# ACT_REG.net
KiCad netlist of a schematic drawn in Altium Designer
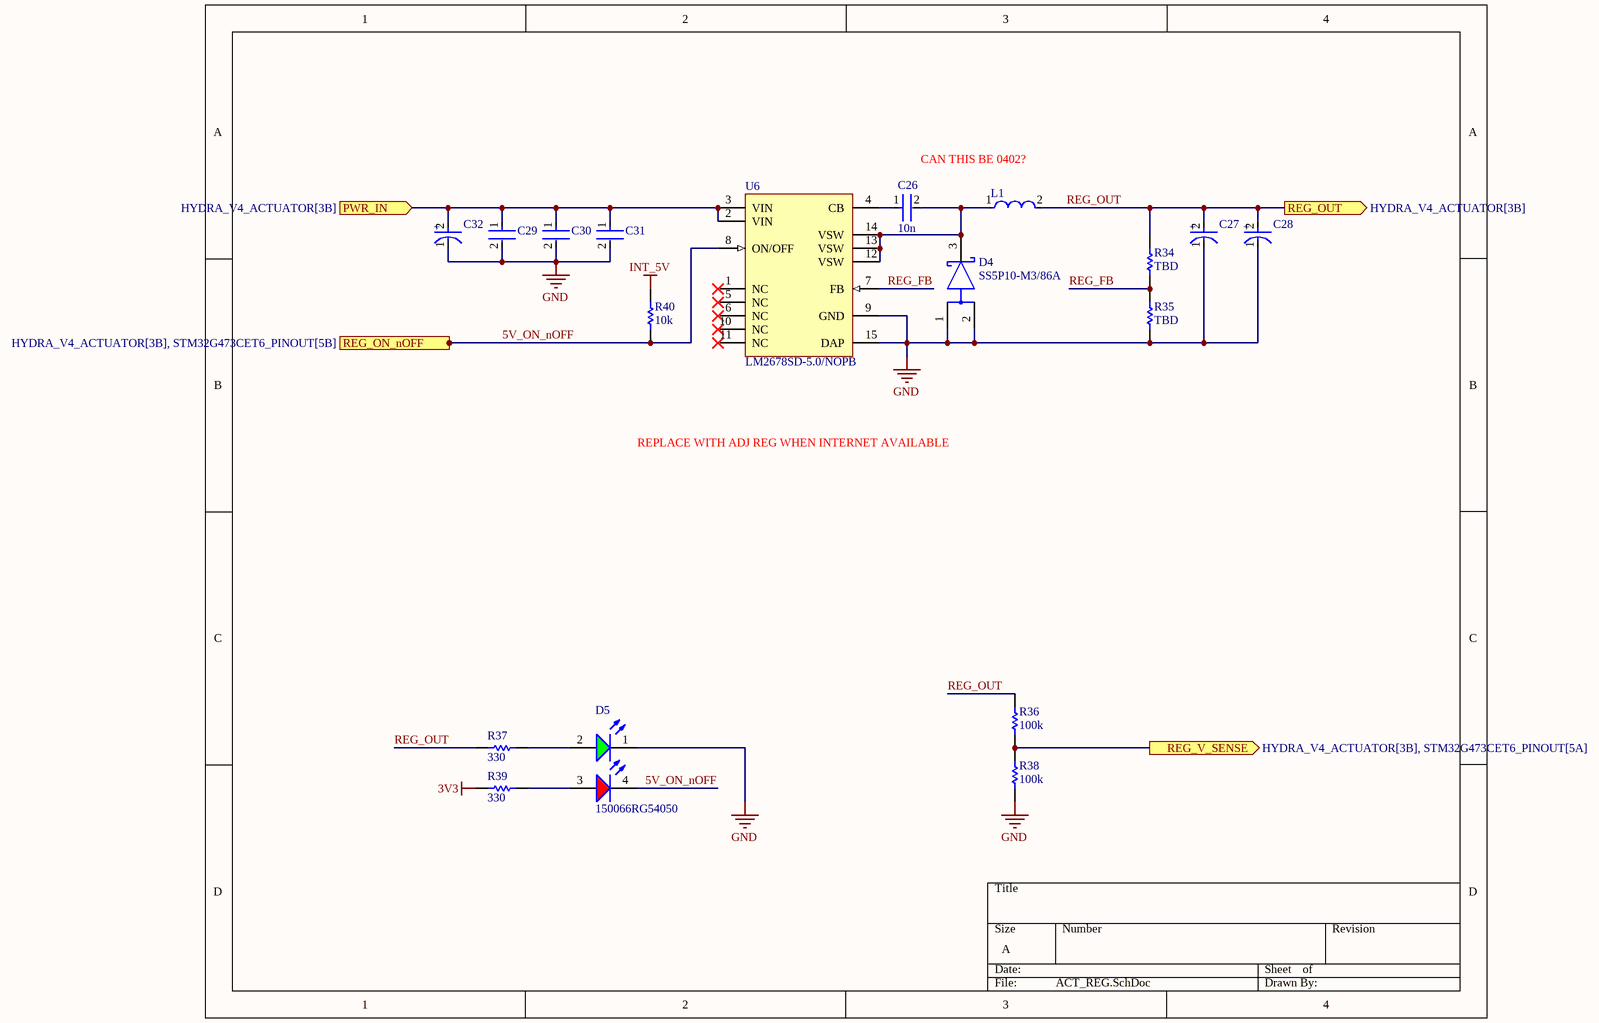
[diagram p0: ACT_REG.SchDoc]

(export (version "E")
  (design (tool "Eeschema 10.0.6"))
  (components
    (comp (ref "C26")
      (value "10n")
      (footprint "FP-0402-L_1_0_0_05-W_0_5-IPC_A")
      (description "LARGE PADS, 0402 CAP, CHANGE COMMENT TO MATCH REAL P/N")
      (libsource (lib "Space Concordia") (part "b4654b650e69147ec39a6b967a45e02"))
    )
    (comp (ref "C27")
      (value "10TPC68M")
      (footprint "FP-POSCAP-D2-MFG")
      (description "Molded Tantalum Polymer Capacitor 68uF 20% 10V life 2000Hours SMD 2917")
      (fields (field (name "VOLTAGE") "10V") (field (name "TOLERANCE") "20%"))
      (libsource (lib "Altium Content Vault") (part "a00bbbee19879c290e62620ae7e47b1"))
    )
    (comp (ref "C28")
      (value "10TPC68M")
      (footprint "FP-POSCAP-D2-MFG")
      (description "Molded Tantalum Polymer Capacitor 68uF 20% 10V life 2000Hours SMD 2917")
      (fields (field (name "VOLTAGE") "10V") (field (name "TOLERANCE") "20%"))
      (libsource (lib "Altium Content Vault") (part "a00bbbee19879c290e62620ae7e47b1"))
    )
    (comp (ref "C29")
      (value "C2012X5R1V156M125AC")
      (footprint "FP-C2012-125-0_2-MFG")
      (description "Multilayer Ceramic Capacitors 15μF ±20% 35V X5R SMD 0805")
      (fields (field (name "TOLERANCE") "20%"))
      (libsource (lib "Altium Content Vault") (part "b4654b650e69147ec39a6b967a45e02"))
    )
    (comp (ref "C30")
      (value "C2012X5R1V156M125AC")
      (footprint "FP-C2012-125-0_2-MFG")
      (description "Multilayer Ceramic Capacitors 15μF ±20% 35V X5R SMD 0805")
      (fields (field (name "TOLERANCE") "20%"))
      (libsource (lib "Altium Content Vault") (part "b4654b650e69147ec39a6b967a45e02"))
    )
    (comp (ref "C31")
      (value "C2012X5R1V156M125AC")
      (footprint "FP-C2012-125-0_2-MFG")
      (description "Multilayer Ceramic Capacitors 15μF ±20% 35V X5R SMD 0805")
      (fields (field (name "TOLERANCE") "20%"))
      (libsource (lib "Altium Content Vault") (part "b4654b650e69147ec39a6b967a45e02"))
    )
    (comp (ref "C32")
      (value "10TPC68M")
      (footprint "FP-POSCAP-D2-MFG")
      (description "Molded Tantalum Polymer Capacitor 68uF 20% 10V life 2000Hours SMD 2917")
      (fields (field (name "VOLTAGE") "10V") (field (name "TOLERANCE") "20%"))
      (libsource (lib "Altium Content Vault") (part "a00bbbee19879c290e62620ae7e47b1"))
    )
    (comp (ref "D4")
      (value "SS5P10-M3/86A")
      (footprint "FP-95570-MFG")
      (description "DIODE SCHOTTKY 100V 5A TO277A")
      (libsource (lib "Altium Content Vault") (part "03725f8997c85b601c823eea96032f8"))
    )
    (comp (ref "D5")
      (value "150066RG54050")
      (footprint "WL-SBCD_0606")
      (description "Led, Red/Grn, 180Mcd/230Mcd, 624Nm/525Nm Rohs Compliant: Yes")
      (fields (field (name "SOURCE") "rgled.SchLib"))
      (libsource (lib "Space Concordia") (part "CMP-004-00034-2"))
    )
    (comp (ref "L1")
      (value "IHLP4040DZER220M11")
      (footprint "FP-IHLP-4040DZ-FP_3_124x3-MFG")
      (description "Commercial Inductors, Low DCR Series 22uH 5A 66mΩ 20%")
      (fields (field (name "TOLERANCE") "20%"))
      (libsource (lib "Altium Content Vault") (part "725321dda6339637d4d059423bc1c3c"))
    )
    (comp (ref "R34")
      (value "TBD")
      (footprint "R0603B")
      (description "Resistor")
      (libsource (lib "Space Concordia") (part "Resistor"))
    )
    (comp (ref "R35")
      (value "TBD")
      (footprint "R0603B")
      (description "Resistor")
      (libsource (lib "Space Concordia") (part "Resistor"))
    )
    (comp (ref "R36")
      (value "100k")
      (footprint "R0603B")
      (description "Resistor")
      (libsource (lib "Space Concordia") (part "Resistor"))
    )
    (comp (ref "R37")
      (value "330")
      (footprint "R0603B")
      (description "Resistor")
      (libsource (lib "Space Concordia") (part "Resistor"))
    )
    (comp (ref "R38")
      (value "100k")
      (footprint "R0603B")
      (description "Resistor")
      (libsource (lib "Space Concordia") (part "Resistor"))
    )
    (comp (ref "R39")
      (value "330")
      (footprint "R0603B")
      (description "Resistor")
      (libsource (lib "Space Concordia") (part "Resistor"))
    )
    (comp (ref "R40")
      (value "10k")
      (footprint "R0603B")
      (description "Resistor")
      (libsource (lib "Space Concordia") (part "Resistor"))
    )
    (comp (ref "U6")
      (value "LM2678SD-5.0/NOPB")
      (footprint "NHM0014A_V")
      (description "SIMPLE SWITCHER® High Efficiency 5A Step-Down Voltage Regulator, 14-pin LLP, Pb-Free")
      (fields (field (name "MANUFACTURER") "Texas Instruments"))
      (libsource (lib "Altium Content Vault") (part "PM-REG-LM2678SD"))
    )
  )
  (nets
    (net (code "1") (name "/5V_ON_nOFF") (class "Default")
      (node (ref "D5") (pin "4") (pinfunction "K_4") (pintype "passive"))
      (node (ref "R40") (pin "1") (pinfunction "1_1") (pintype "passive"))
      (node (ref "U6") (pin "8") (pinfunction "ON/OFF_8") (pintype "input"))
    )
    (net (code "2") (name "/PWR_IN") (class "Default")
      (node (ref "C29") (pin "1") (pinfunction "1_1") (pintype "passive"))
      (node (ref "C30") (pin "1") (pinfunction "1_1") (pintype "passive"))
      (node (ref "C31") (pin "1") (pinfunction "1_1") (pintype "passive"))
      (node (ref "C32") (pin "2") (pinfunction "A_2") (pintype "passive"))
      (node (ref "U6") (pin "2") (pinfunction "VIN_2") (pintype "power_in"))
      (node (ref "U6") (pin "3") (pinfunction "VIN_3") (pintype "power_in"))
    )
    (net (code "3") (name "/REG_FB") (class "Default")
      (node (ref "R34") (pin "1") (pinfunction "1_1") (pintype "passive"))
      (node (ref "R35") (pin "2") (pinfunction "2_2") (pintype "passive"))
      (node (ref "U6") (pin "7") (pinfunction "FB_7") (pintype "input"))
    )
    (net (code "4") (name "/REG_OUT") (class "Default")
      (node (ref "C27") (pin "2") (pinfunction "A_2") (pintype "passive"))
      (node (ref "C28") (pin "2") (pinfunction "A_2") (pintype "passive"))
      (node (ref "L1") (pin "2") (pinfunction "2_2") (pintype "passive"))
      (node (ref "R34") (pin "2") (pinfunction "2_2") (pintype "passive"))
      (node (ref "R36") (pin "2") (pinfunction "2_2") (pintype "passive"))
      (node (ref "R37") (pin "2") (pinfunction "2_2") (pintype "passive"))
    )
    (net (code "5") (name "/REG_V_SENSE") (class "Default")
      (node (ref "R36") (pin "1") (pinfunction "1_1") (pintype "passive"))
      (node (ref "R38") (pin "2") (pinfunction "2_2") (pintype "passive"))
    )
    (net (code "6") (name "3V3") (class "Default")
      (node (ref "R39") (pin "2") (pinfunction "2_2") (pintype "passive"))
    )
    (net (code "7") (name "GND") (class "Default")
      (node (ref "C27") (pin "1") (pinfunction "C_1") (pintype "passive"))
      (node (ref "C28") (pin "1") (pinfunction "C_1") (pintype "passive"))
      (node (ref "C29") (pin "2") (pinfunction "2_2") (pintype "passive"))
      (node (ref "C30") (pin "2") (pinfunction "2_2") (pintype "passive"))
      (node (ref "C31") (pin "2") (pinfunction "2_2") (pintype "passive"))
      (node (ref "C32") (pin "1") (pinfunction "C_1") (pintype "passive"))
      (node (ref "D4") (pin "1") (pinfunction "A_1") (pintype "passive"))
      (node (ref "D4") (pin "2") (pinfunction "A_2") (pintype "passive"))
      (node (ref "D5") (pin "1") (pinfunction "K_1") (pintype "passive"))
      (node (ref "R35") (pin "1") (pinfunction "1_1") (pintype "passive"))
      (node (ref "R38") (pin "1") (pinfunction "1_1") (pintype "passive"))
      (node (ref "U6") (pin "15") (pinfunction "DAP_15") (pintype "power_in"))
      (node (ref "U6") (pin "9") (pinfunction "GND_9") (pintype "power_in"))
    )
    (net (code "8") (name "INT_5V") (class "Default")
      (node (ref "R40") (pin "2") (pinfunction "2_2") (pintype "passive"))
    )
    (net (code "9") (name "Net-(D4-C)") (class "Default")
      (node (ref "C26") (pin "2") (pinfunction "2_2") (pintype "passive"))
      (node (ref "D4") (pin "3") (pinfunction "C_3") (pintype "passive"))
      (node (ref "L1") (pin "1") (pinfunction "1_1") (pintype "passive"))
      (node (ref "U6") (pin "12") (pinfunction "VSW_12") (pintype "power_in"))
      (node (ref "U6") (pin "13") (pinfunction "VSW_13") (pintype "power_in"))
      (node (ref "U6") (pin "14") (pinfunction "VSW_14") (pintype "power_in"))
    )
    (net (code "10") (name "Net-(D5-A-Pad2)") (class "Default")
      (node (ref "D5") (pin "2") (pinfunction "A_2") (pintype "passive"))
      (node (ref "R37") (pin "1") (pinfunction "1_1") (pintype "passive"))
    )
    (net (code "11") (name "Net-(D5-A-Pad3)") (class "Default")
      (node (ref "D5") (pin "3") (pinfunction "A_3") (pintype "passive"))
      (node (ref "R39") (pin "1") (pinfunction "1_1") (pintype "passive"))
    )
    (net (code "12") (name "Net-(U6-CB)") (class "Default")
      (node (ref "C26") (pin "1") (pinfunction "1_1") (pintype "passive"))
      (node (ref "U6") (pin "4") (pinfunction "CB_4") (pintype "passive"))
    )
    (net (code "13") (name "unconnected-(U6-NC-Pad1)") (class "Default")
      (node (ref "U6") (pin "1") (pinfunction "NC_1") (pintype "passive+no_connect"))
    )
    (net (code "14") (name "unconnected-(U6-NC-Pad5)") (class "Default")
      (node (ref "U6") (pin "5") (pinfunction "NC_5") (pintype "passive+no_connect"))
    )
    (net (code "15") (name "unconnected-(U6-NC-Pad6)") (class "Default")
      (node (ref "U6") (pin "6") (pinfunction "NC_6") (pintype "passive+no_connect"))
    )
    (net (code "16") (name "unconnected-(U6-NC-Pad10)") (class "Default")
      (node (ref "U6") (pin "10") (pinfunction "NC_10") (pintype "passive+no_connect"))
    )
    (net (code "17") (name "unconnected-(U6-NC-Pad11)") (class "Default")
      (node (ref "U6") (pin "11") (pinfunction "NC_11") (pintype "passive+no_connect"))
    )
  )
)
